# SimpleShield.net
KiCad netlist of a schematic drawn in EAGLE
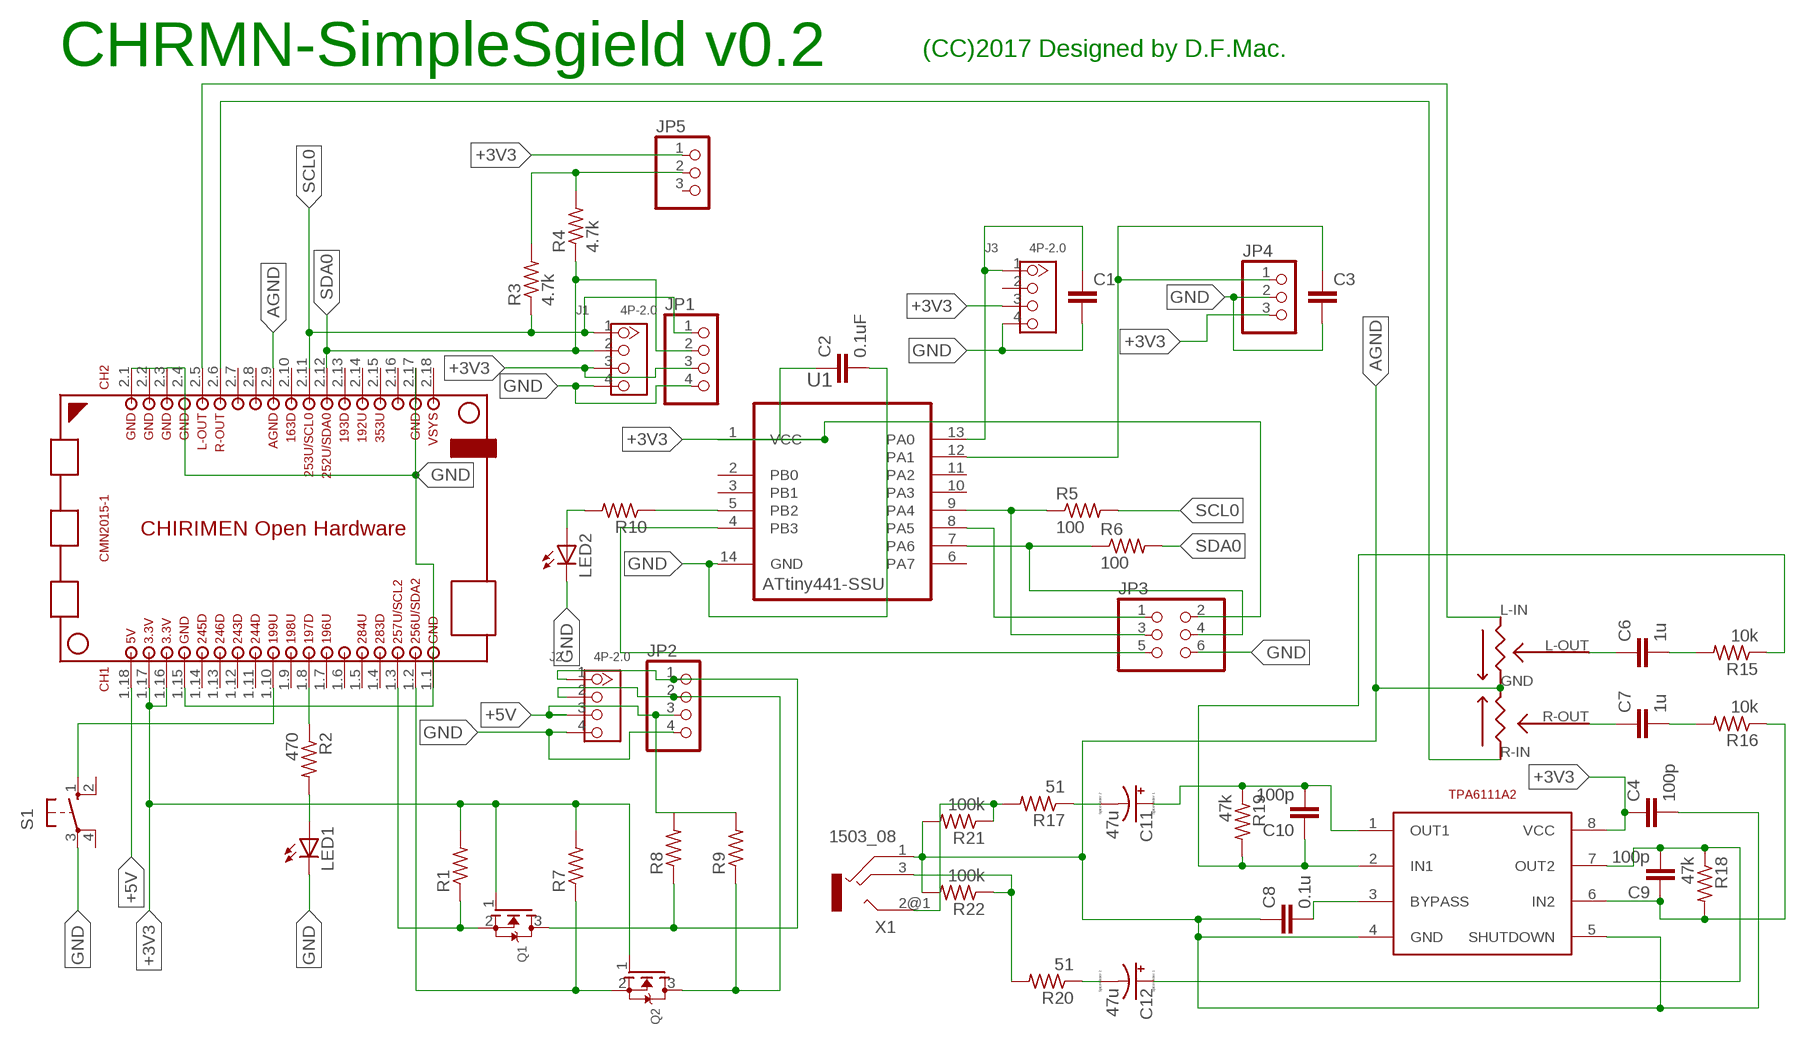
[diagram p0: schematic, sheet 1]

(export (version "E")
  (design (tool "Eeschema 10.0.6"))
  (components
    (comp (ref "C1")
      (value "C-EUC0805")
      (footprint "eagle-import:C0805")
      (libsource (lib "eagle-import") (part "C-EUC0805"))
    )
    (comp (ref "C2")
      (value "0.1uF")
      (footprint "eagle-import:C0805")
      (libsource (lib "eagle-import") (part "C-EUC0805"))
    )
    (comp (ref "C3")
      (value "C-EUC0805")
      (footprint "eagle-import:C0805")
      (libsource (lib "eagle-import") (part "C-EUC0805"))
    )
    (comp (ref "C4")
      (value "100p")
      (footprint "eagle-import:C0603K")
      (libsource (lib "eagle-import") (part "resistor_C-EUC0603K"))
    )
    (comp (ref "C6")
      (value "1u")
      (footprint "eagle-import:C0603K")
      (libsource (lib "eagle-import") (part "resistor_C-EUC0603K"))
    )
    (comp (ref "C7")
      (value "1u")
      (footprint "eagle-import:C0603K")
      (libsource (lib "eagle-import") (part "resistor_C-EUC0603K"))
    )
    (comp (ref "C8")
      (value "0.1u")
      (footprint "eagle-import:C0603K")
      (libsource (lib "eagle-import") (part "resistor_C-EUC0603K"))
    )
    (comp (ref "C9")
      (value "100p")
      (footprint "eagle-import:C0603K")
      (libsource (lib "eagle-import") (part "resistor_C-EUC0603K"))
    )
    (comp (ref "C10")
      (value "100p")
      (footprint "eagle-import:C0603K")
      (libsource (lib "eagle-import") (part "resistor_C-EUC0603K"))
    )
    (comp (ref "C11")
      (value "47u")
      (footprint "eagle-import:153CLV-0605")
      (libsource (lib "eagle-import") (part "CPOL-US153CLV-0605"))
    )
    (comp (ref "C12")
      (value "47u")
      (footprint "eagle-import:153CLV-0605")
      (libsource (lib "eagle-import") (part "CPOL-US153CLV-0605"))
    )
    (comp (ref "J1")
      (value "4P-2.0")
      (footprint "eagle-import:HW4-2.0")
      (libsource (lib "eagle-import") (part "GROVE-CONNECTOR-DIP(4P-2.0)"))
    )
    (comp (ref "J2")
      (value "4P-2.0")
      (footprint "eagle-import:HW4-2.0")
      (libsource (lib "eagle-import") (part "GROVE-CONNECTOR-DIP(4P-2.0)"))
    )
    (comp (ref "J3")
      (value "4P-2.0")
      (footprint "eagle-import:HW4-2.0")
      (libsource (lib "eagle-import") (part "GROVE-CONNECTOR-DIP(4P-2.0)"))
    )
    (comp (ref "JP1")
      (value "PINHD-1X4")
      (footprint "eagle-import:1X04")
      (libsource (lib "eagle-import") (part "PINHD-1X4"))
    )
    (comp (ref "JP2")
      (value "PINHD-1X4")
      (footprint "eagle-import:1X04")
      (libsource (lib "eagle-import") (part "PINHD-1X4"))
    )
    (comp (ref "JP3")
      (value "PINHD-2X3")
      (footprint "eagle-import:2X03")
      (libsource (lib "eagle-import") (part "PINHD-2X3"))
    )
    (comp (ref "JP4")
      (value "PINHD-1X3")
      (footprint "eagle-import:1X03")
      (libsource (lib "eagle-import") (part "PINHD-1X3"))
    )
    (comp (ref "JP5")
      (value "PINHD-1X3")
      (footprint "eagle-import:1X03")
      (libsource (lib "eagle-import") (part "PINHD-1X3"))
    )
    (comp (ref "LED1")
      (value "LED3MM")
      (footprint "eagle-import:LED3MM")
      (libsource (lib "eagle-import") (part "LED3MM"))
    )
    (comp (ref "LED2")
      (value "LED3MM")
      (footprint "eagle-import:LED3MM")
      (libsource (lib "eagle-import") (part "LED3MM"))
    )
    (comp (ref "Q1")
      (value "MOSFET-NREFLOW")
      (footprint "eagle-import:SOT23")
      (libsource (lib "eagle-import") (part "MOSFET-NREFLOW"))
    )
    (comp (ref "Q2")
      (value "MOSFET-NREFLOW")
      (footprint "eagle-import:SOT23")
      (libsource (lib "eagle-import") (part "MOSFET-NREFLOW"))
    )
    (comp (ref "R1")
      (value "R-US_R0603")
      (footprint "eagle-import:R0603")
      (libsource (lib "eagle-import") (part "R-US_R0603"))
    )
    (comp (ref "R2")
      (value "470")
      (footprint "eagle-import:R0603")
      (libsource (lib "eagle-import") (part "R-US_R0603"))
    )
    (comp (ref "R3")
      (value "4.7k")
      (footprint "eagle-import:R0603")
      (libsource (lib "eagle-import") (part "R-US_R0603"))
    )
    (comp (ref "R4")
      (value "4.7k")
      (footprint "eagle-import:R0603")
      (libsource (lib "eagle-import") (part "R-US_R0603"))
    )
    (comp (ref "R5")
      (value "100")
      (footprint "eagle-import:R0603")
      (libsource (lib "eagle-import") (part "R-US_R0603"))
    )
    (comp (ref "R6")
      (value "100")
      (footprint "eagle-import:R0603")
      (libsource (lib "eagle-import") (part "R-US_R0603"))
    )
    (comp (ref "R7")
      (value "R-US_R0603")
      (footprint "eagle-import:R0603")
      (libsource (lib "eagle-import") (part "R-US_R0603"))
    )
    (comp (ref "R8")
      (value "R-US_R0603")
      (footprint "eagle-import:R0603")
      (libsource (lib "eagle-import") (part "R-US_R0603"))
    )
    (comp (ref "R9")
      (value "R-US_R0603")
      (footprint "eagle-import:R0603")
      (libsource (lib "eagle-import") (part "R-US_R0603"))
    )
    (comp (ref "R10")
      (value "R-US_R0603")
      (footprint "eagle-import:R0603")
      (libsource (lib "eagle-import") (part "R-US_R0603"))
    )
    (comp (ref "R15")
      (value "10k")
      (footprint "eagle-import:R0603")
      (libsource (lib "eagle-import") (part "R-US_R0603"))
    )
    (comp (ref "R16")
      (value "10k")
      (footprint "eagle-import:R0603")
      (libsource (lib "eagle-import") (part "R-US_R0603"))
    )
    (comp (ref "R17")
      (value "51")
      (footprint "eagle-import:R0603")
      (libsource (lib "eagle-import") (part "R-US_R0603"))
    )
    (comp (ref "R18")
      (value "47k")
      (footprint "eagle-import:R0603")
      (libsource (lib "eagle-import") (part "R-US_R0603"))
    )
    (comp (ref "R19")
      (value "47k")
      (footprint "eagle-import:R0603")
      (libsource (lib "eagle-import") (part "R-US_R0603"))
    )
    (comp (ref "R20")
      (value "51")
      (footprint "eagle-import:R0603")
      (libsource (lib "eagle-import") (part "R-US_R0603"))
    )
    (comp (ref "R21")
      (value "100k")
      (footprint "eagle-import:R0603")
      (libsource (lib "eagle-import") (part "R-US_R0603"))
    )
    (comp (ref "R22")
      (value "100k")
      (footprint "eagle-import:R0603")
      (libsource (lib "eagle-import") (part "R-US_R0603"))
    )
    (comp (ref "S1")
      (value "10-XX")
      (footprint "eagle-import:B3F-10XX")
      (fields (field (name "MPN") "B3F-1000"))
      (libsource (lib "eagle-import") (part "10-XX"))
    )
    (comp (ref "U$1")
      (value "CMN2015-1SMALL")
      (footprint "eagle-import:CHMN2015-1-SMALL")
      (libsource (lib "eagle-import") (part "CMN2015-1SMALL"))
    )
    (comp (ref "U$4")
      (value "5PIN-RADIO-POT")
      (footprint "eagle-import:5PIN-RADIO-POT")
      (libsource (lib "eagle-import") (part "5PIN-RADIO-POT"))
    )
    (comp (ref "U$5")
      (value "TPA6111A2")
      (footprint "eagle-import:MSOP8")
      (libsource (lib "eagle-import") (part "TPA6111A2"))
    )
    (comp (ref "U1")
      (value "ATTINY44A-SSU")
      (footprint "eagle-import:SOIC127P600X175-14N")
      (libsource (lib "eagle-import") (part "ATTINY44A-SSU"))
    )
    (comp (ref "X1")
      (value "1503_08")
      (footprint "eagle-import:1503_08")
      (libsource (lib "eagle-import") (part "1503_?08"))
    )
  )
  (nets
    (net (code "1") (name "+3V3") (class "Default")
      (node (ref "C2") (pin "1") (pinfunction "1_1") (pintype "passive"))
      (node (ref "C4") (pin "1") (pinfunction "1_1") (pintype "passive"))
      (node (ref "J1") (pin "3") (pinfunction "3_3") (pintype "bidirectional"))
      (node (ref "J3") (pin "3") (pinfunction "3_3") (pintype "bidirectional"))
      (node (ref "JP1") (pin "3") (pinfunction "3_3") (pintype "passive"))
      (node (ref "JP3") (pin "2") (pinfunction "2_2") (pintype "passive"))
      (node (ref "JP4") (pin "3") (pinfunction "3_3") (pintype "passive"))
      (node (ref "JP5") (pin "1") (pinfunction "1_1") (pintype "passive"))
      (node (ref "Q1") (pin "1") (pinfunction "G_1") (pintype "bidirectional"))
      (node (ref "Q2") (pin "1") (pinfunction "G_1") (pintype "bidirectional"))
      (node (ref "R1") (pin "2") (pinfunction "2_2") (pintype "passive"))
      (node (ref "R7") (pin "2") (pinfunction "2_2") (pintype "passive"))
      (node (ref "U$1") (pin "1.16") (pinfunction "CH1-16_1.16") (pintype "bidirectional"))
      (node (ref "U$1") (pin "1.17") (pinfunction "CH1-17_1.17") (pintype "bidirectional"))
      (node (ref "U$5") (pin "8") (pinfunction "VCC_8") (pintype "bidirectional"))
      (node (ref "U1") (pin "1") (pinfunction "VCC_1") (pintype "power_in"))
    )
    (net (code "2") (name "+5V") (class "Default")
      (node (ref "J2") (pin "3") (pinfunction "3_3") (pintype "bidirectional"))
      (node (ref "JP2") (pin "3") (pinfunction "3_3") (pintype "passive"))
      (node (ref "R8") (pin "2") (pinfunction "2_2") (pintype "passive"))
      (node (ref "R9") (pin "2") (pinfunction "2_2") (pintype "passive"))
      (node (ref "U$1") (pin "1.18") (pinfunction "CH1-18_1.18") (pintype "bidirectional"))
    )
    (net (code "3") (name "AGND") (class "Default")
      (node (ref "C4") (pin "2") (pinfunction "2_2") (pintype "passive"))
      (node (ref "C8") (pin "1") (pinfunction "1_1") (pintype "passive"))
      (node (ref "R21") (pin "2") (pinfunction "2_2") (pintype "passive"))
      (node (ref "R22") (pin "2") (pinfunction "2_2") (pintype "passive"))
      (node (ref "U$1") (pin "2.9") (pinfunction "CH2-9_2.9") (pintype "bidirectional"))
      (node (ref "U$4") (pin "GND") (pinfunction "GND_GND") (pintype "bidirectional"))
      (node (ref "U$5") (pin "4") (pinfunction "GND_4") (pintype "bidirectional"))
      (node (ref "U$5") (pin "5") (pinfunction "SHUTDOWN_5") (pintype "bidirectional"))
      (node (ref "X1") (pin "1") (pinfunction "GND_1") (pintype "passive"))
    )
    (net (code "4") (name "GND") (class "Default")
      (node (ref "C1") (pin "2") (pinfunction "2_2") (pintype "passive"))
      (node (ref "C2") (pin "2") (pinfunction "2_2") (pintype "passive"))
      (node (ref "C3") (pin "2") (pinfunction "2_2") (pintype "passive"))
      (node (ref "J1") (pin "4") (pinfunction "4_4") (pintype "bidirectional"))
      (node (ref "J2") (pin "4") (pinfunction "4_4") (pintype "bidirectional"))
      (node (ref "J3") (pin "4") (pinfunction "4_4") (pintype "bidirectional"))
      (node (ref "JP1") (pin "4") (pinfunction "4_4") (pintype "passive"))
      (node (ref "JP2") (pin "4") (pinfunction "4_4") (pintype "passive"))
      (node (ref "JP3") (pin "6") (pinfunction "6_6") (pintype "passive"))
      (node (ref "JP4") (pin "2") (pinfunction "2_2") (pintype "passive"))
      (node (ref "LED1") (pin "K") (pinfunction "C_K") (pintype "passive"))
      (node (ref "LED2") (pin "K") (pinfunction "C_K") (pintype "passive"))
      (node (ref "S1") (pin "3") (pinfunction "P_3") (pintype "passive"))
      (node (ref "U$1") (pin "1.1") (pinfunction "CH1-1_1.1") (pintype "bidirectional"))
      (node (ref "U$1") (pin "1.15") (pinfunction "CH1-15_1.15") (pintype "bidirectional"))
      (node (ref "U$1") (pin "2.1") (pinfunction "CH2-1_2.1") (pintype "bidirectional"))
      (node (ref "U$1") (pin "2.17") (pinfunction "CH2-17_2.17") (pintype "bidirectional"))
      (node (ref "U$1") (pin "2.2") (pinfunction "CH2-2_2.2") (pintype "bidirectional"))
      (node (ref "U$1") (pin "2.3") (pinfunction "CH2-3_2.3") (pintype "bidirectional"))
      (node (ref "U$1") (pin "2.4") (pinfunction "CH2-4_2.4") (pintype "bidirectional"))
      (node (ref "U1") (pin "14") (pinfunction "GND_14") (pintype "power_in"))
    )
    (net (code "5") (name "Net-(C6-Pad2)") (class "Default")
      (node (ref "C6") (pin "2") (pinfunction "2_2") (pintype "passive"))
      (node (ref "R15") (pin "2") (pinfunction "2_2") (pintype "passive"))
    )
    (net (code "6") (name "Net-(C7-Pad2)") (class "Default")
      (node (ref "C7") (pin "2") (pinfunction "2_2") (pintype "passive"))
      (node (ref "R16") (pin "2") (pinfunction "2_2") (pintype "passive"))
    )
    (net (code "7") (name "Net-(C11-Pad-)") (class "Default")
      (node (ref "C11") (pin "-") (pinfunction "-_-") (pintype "passive"))
      (node (ref "R17") (pin "1") (pinfunction "1_1") (pintype "passive"))
    )
    (net (code "8") (name "Net-(C12-Pad-)") (class "Default")
      (node (ref "C12") (pin "-") (pinfunction "-_-") (pintype "passive"))
      (node (ref "R20") (pin "1") (pinfunction "1_1") (pintype "passive"))
    )
    (net (code "9") (name "Net-(JP5-Pad2)") (class "Default")
      (node (ref "JP5") (pin "2") (pinfunction "2_2") (pintype "passive"))
      (node (ref "R3") (pin "2") (pinfunction "2_2") (pintype "passive"))
      (node (ref "R4") (pin "2") (pinfunction "2_2") (pintype "passive"))
    )
    (net (code "10") (name "Net-(LED1-PadA)") (class "Default")
      (node (ref "LED1") (pin "A") (pinfunction "A_A") (pintype "passive"))
      (node (ref "R2") (pin "2") (pinfunction "2_2") (pintype "passive"))
    )
    (net (code "11") (name "Net-(LED2-PadA)") (class "Default")
      (node (ref "LED2") (pin "A") (pinfunction "A_A") (pintype "passive"))
      (node (ref "R10") (pin "2") (pinfunction "2_2") (pintype "passive"))
    )
    (net (code "12") (name "Net-(Q1-D)") (class "Default")
      (node (ref "J2") (pin "1") (pinfunction "1_1") (pintype "bidirectional"))
      (node (ref "JP2") (pin "1") (pinfunction "1_1") (pintype "passive"))
      (node (ref "Q1") (pin "3") (pinfunction "D_3") (pintype "bidirectional"))
      (node (ref "R8") (pin "1") (pinfunction "1_1") (pintype "passive"))
    )
    (net (code "13") (name "Net-(Q1-S)") (class "Default")
      (node (ref "Q1") (pin "2") (pinfunction "S_2") (pintype "bidirectional"))
      (node (ref "R1") (pin "1") (pinfunction "1_1") (pintype "passive"))
      (node (ref "U$1") (pin "1.3") (pinfunction "CH1-3_1.3") (pintype "bidirectional"))
    )
    (net (code "14") (name "Net-(Q2-D)") (class "Default")
      (node (ref "J2") (pin "2") (pinfunction "2_2") (pintype "bidirectional"))
      (node (ref "JP2") (pin "2") (pinfunction "2_2") (pintype "passive"))
      (node (ref "Q2") (pin "3") (pinfunction "D_3") (pintype "bidirectional"))
      (node (ref "R9") (pin "1") (pinfunction "1_1") (pintype "passive"))
    )
    (net (code "15") (name "Net-(Q2-S)") (class "Default")
      (node (ref "Q2") (pin "2") (pinfunction "S_2") (pintype "bidirectional"))
      (node (ref "R7") (pin "1") (pinfunction "1_1") (pintype "passive"))
      (node (ref "U$1") (pin "1.2") (pinfunction "CH1-2_1.2") (pintype "bidirectional"))
    )
    (net (code "16") (name "Net-(S1-S)") (class "Default")
      (node (ref "S1") (pin "1") (pinfunction "S_1") (pintype "passive"))
      (node (ref "U$1") (pin "1.10") (pinfunction "CH1-10_1.10") (pintype "bidirectional"))
    )
    (net (code "17") (name "Net-(U$1-CH1-8)") (class "Default")
      (node (ref "R2") (pin "1") (pinfunction "1_1") (pintype "passive"))
      (node (ref "U$1") (pin "1.8") (pinfunction "CH1-8_1.8") (pintype "bidirectional"))
    )
    (net (code "18") (name "Net-(U$1-CH2-5)") (class "Default")
      (node (ref "U$1") (pin "2.5") (pinfunction "CH2-5_2.5") (pintype "bidirectional"))
      (node (ref "U$4") (pin "L-IN") (pinfunction "IN-L_L-IN") (pintype "bidirectional"))
    )
    (net (code "19") (name "Net-(U$1-CH2-6)") (class "Default")
      (node (ref "U$1") (pin "2.6") (pinfunction "CH2-6_2.6") (pintype "bidirectional"))
      (node (ref "U$4") (pin "R-IN") (pinfunction "IN-R_R-IN") (pintype "bidirectional"))
    )
    (net (code "20") (name "Net-(U$4-OUT-L)") (class "Default")
      (node (ref "C6") (pin "1") (pinfunction "1_1") (pintype "passive"))
      (node (ref "U$4") (pin "L-OUT") (pinfunction "OUT-L_L-OUT") (pintype "bidirectional"))
    )
    (net (code "21") (name "Net-(U$4-OUT-R)") (class "Default")
      (node (ref "C7") (pin "1") (pinfunction "1_1") (pintype "passive"))
      (node (ref "U$4") (pin "R-OUT") (pinfunction "OUT-R_R-OUT") (pintype "bidirectional"))
    )
    (net (code "22") (name "Net-(U$5-BYPASS)") (class "Default")
      (node (ref "C8") (pin "2") (pinfunction "2_2") (pintype "passive"))
      (node (ref "U$5") (pin "3") (pinfunction "BYPASS_3") (pintype "bidirectional"))
    )
    (net (code "23") (name "Net-(U$5-IN1)") (class "Default")
      (node (ref "C10") (pin "1") (pinfunction "1_1") (pintype "passive"))
      (node (ref "R15") (pin "1") (pinfunction "1_1") (pintype "passive"))
      (node (ref "R19") (pin "2") (pinfunction "2_2") (pintype "passive"))
      (node (ref "U$5") (pin "2") (pinfunction "IN1_2") (pintype "bidirectional"))
    )
    (net (code "24") (name "Net-(U$5-IN2)") (class "Default")
      (node (ref "C9") (pin "1") (pinfunction "1_1") (pintype "passive"))
      (node (ref "R16") (pin "1") (pinfunction "1_1") (pintype "passive"))
      (node (ref "R18") (pin "2") (pinfunction "2_2") (pintype "passive"))
      (node (ref "U$5") (pin "6") (pinfunction "IN2_6") (pintype "bidirectional"))
    )
    (net (code "25") (name "Net-(U$5-OUT1)") (class "Default")
      (node (ref "C10") (pin "2") (pinfunction "2_2") (pintype "passive"))
      (node (ref "C11") (pin "+") (pinfunction "+_+") (pintype "passive"))
      (node (ref "R19") (pin "1") (pinfunction "1_1") (pintype "passive"))
      (node (ref "U$5") (pin "1") (pinfunction "OUT1_1") (pintype "bidirectional"))
    )
    (net (code "26") (name "Net-(U$5-OUT2)") (class "Default")
      (node (ref "C12") (pin "+") (pinfunction "+_+") (pintype "passive"))
      (node (ref "C9") (pin "2") (pinfunction "2_2") (pintype "passive"))
      (node (ref "R18") (pin "1") (pinfunction "1_1") (pintype "passive"))
      (node (ref "U$5") (pin "7") (pinfunction "OUT2_7") (pintype "bidirectional"))
    )
    (net (code "27") (name "Net-(U1-PA0)") (class "Default")
      (node (ref "C1") (pin "1") (pinfunction "1_1") (pintype "passive"))
      (node (ref "J3") (pin "1") (pinfunction "1_1") (pintype "bidirectional"))
      (node (ref "U1") (pin "13") (pinfunction "PA0_13") (pintype "bidirectional"))
    )
    (net (code "28") (name "Net-(U1-PA1)") (class "Default")
      (node (ref "C3") (pin "1") (pinfunction "1_1") (pintype "passive"))
      (node (ref "JP4") (pin "1") (pinfunction "1_1") (pintype "passive"))
      (node (ref "U1") (pin "12") (pinfunction "PA1_12") (pintype "bidirectional"))
    )
    (net (code "29") (name "Net-(U1-PA4)") (class "Default")
      (node (ref "JP3") (pin "3") (pinfunction "3_3") (pintype "passive"))
      (node (ref "R5") (pin "1") (pinfunction "1_1") (pintype "passive"))
      (node (ref "U1") (pin "9") (pinfunction "PA4_9") (pintype "bidirectional"))
    )
    (net (code "30") (name "Net-(U1-PA5)") (class "Default")
      (node (ref "JP3") (pin "1") (pinfunction "1_1") (pintype "passive"))
      (node (ref "U1") (pin "8") (pinfunction "PA5_8") (pintype "bidirectional"))
    )
    (net (code "31") (name "Net-(U1-PA6)") (class "Default")
      (node (ref "JP3") (pin "4") (pinfunction "4_4") (pintype "passive"))
      (node (ref "R6") (pin "1") (pinfunction "1_1") (pintype "passive"))
      (node (ref "U1") (pin "7") (pinfunction "PA6_7") (pintype "bidirectional"))
    )
    (net (code "32") (name "Net-(U1-PB2)") (class "Default")
      (node (ref "R10") (pin "1") (pinfunction "1_1") (pintype "passive"))
      (node (ref "U1") (pin "5") (pinfunction "PB2_5") (pintype "bidirectional"))
    )
    (net (code "33") (name "Net-(U1-PB3)") (class "Default")
      (node (ref "JP3") (pin "5") (pinfunction "5_5") (pintype "passive"))
      (node (ref "U1") (pin "4") (pinfunction "PB3_4") (pintype "bidirectional"))
    )
    (net (code "34") (name "Net-(X1-L)") (class "Default")
      (node (ref "R17") (pin "2") (pinfunction "2_2") (pintype "passive"))
      (node (ref "R21") (pin "1") (pinfunction "1_1") (pintype "passive"))
      (node (ref "X1") (pin "2@1") (pinfunction "L_2@1") (pintype "passive"))
    )
    (net (code "35") (name "Net-(X1-R)") (class "Default")
      (node (ref "R20") (pin "2") (pinfunction "2_2") (pintype "passive"))
      (node (ref "R22") (pin "1") (pinfunction "1_1") (pintype "passive"))
      (node (ref "X1") (pin "3") (pinfunction "R_3") (pintype "passive"))
    )
    (net (code "36") (name "SCL0") (class "Default")
      (node (ref "J1") (pin "1") (pinfunction "1_1") (pintype "bidirectional"))
      (node (ref "JP1") (pin "1") (pinfunction "1_1") (pintype "passive"))
      (node (ref "R3") (pin "1") (pinfunction "1_1") (pintype "passive"))
      (node (ref "R5") (pin "2") (pinfunction "2_2") (pintype "passive"))
      (node (ref "U$1") (pin "2.11") (pinfunction "CH2-11_2.11") (pintype "bidirectional"))
    )
    (net (code "37") (name "SDA0") (class "Default")
      (node (ref "J1") (pin "2") (pinfunction "2_2") (pintype "bidirectional"))
      (node (ref "JP1") (pin "2") (pinfunction "2_2") (pintype "passive"))
      (node (ref "R4") (pin "1") (pinfunction "1_1") (pintype "passive"))
      (node (ref "R6") (pin "2") (pinfunction "2_2") (pintype "passive"))
      (node (ref "U$1") (pin "2.12") (pinfunction "CH2-12_2.12") (pintype "bidirectional"))
    )
    (net (code "38") (name "unconnected-(J3-Pad2)") (class "Default")
      (node (ref "J3") (pin "2") (pinfunction "2_2") (pintype "bidirectional"))
    )
    (net (code "39") (name "unconnected-(JP5-Pad3)") (class "Default")
      (node (ref "JP5") (pin "3") (pinfunction "3_3") (pintype "passive"))
    )
    (net (code "40") (name "unconnected-(S1-P1-Pad4)") (class "Default")
      (node (ref "S1") (pin "4") (pinfunction "P1_4") (pintype "passive"))
    )
    (net (code "41") (name "unconnected-(S1-S1-Pad2)") (class "Default")
      (node (ref "S1") (pin "2") (pinfunction "S1_2") (pintype "passive"))
    )
    (net (code "42") (name "unconnected-(U$1-CH1-4-Pad1.4)") (class "Default")
      (node (ref "U$1") (pin "1.4") (pinfunction "CH1-4_1.4") (pintype "bidirectional"))
    )
    (net (code "43") (name "unconnected-(U$1-CH1-5-Pad1.5)") (class "Default")
      (node (ref "U$1") (pin "1.5") (pinfunction "CH1-5_1.5") (pintype "bidirectional"))
    )
    (net (code "44") (name "unconnected-(U$1-CH1-6-Pad1.6)") (class "Default")
      (node (ref "U$1") (pin "1.6") (pinfunction "CH1-6_1.6") (pintype "bidirectional"))
    )
    (net (code "45") (name "unconnected-(U$1-CH1-7-Pad1.7)") (class "Default")
      (node (ref "U$1") (pin "1.7") (pinfunction "CH1-7_1.7") (pintype "bidirectional"))
    )
    (net (code "46") (name "unconnected-(U$1-CH1-9-Pad1.9)") (class "Default")
      (node (ref "U$1") (pin "1.9") (pinfunction "CH1-9_1.9") (pintype "bidirectional"))
    )
    (net (code "47") (name "unconnected-(U$1-CH1-11-Pad1.11)") (class "Default")
      (node (ref "U$1") (pin "1.11") (pinfunction "CH1-11_1.11") (pintype "bidirectional"))
    )
    (net (code "48") (name "unconnected-(U$1-CH1-12-Pad1.12)") (class "Default")
      (node (ref "U$1") (pin "1.12") (pinfunction "CH1-12_1.12") (pintype "bidirectional"))
    )
    (net (code "49") (name "unconnected-(U$1-CH1-13-Pad1.13)") (class "Default")
      (node (ref "U$1") (pin "1.13") (pinfunction "CH1-13_1.13") (pintype "bidirectional"))
    )
    (net (code "50") (name "unconnected-(U$1-CH1-14-Pad1.14)") (class "Default")
      (node (ref "U$1") (pin "1.14") (pinfunction "CH1-14_1.14") (pintype "bidirectional"))
    )
    (net (code "51") (name "unconnected-(U$1-CH2-7-Pad2.7)") (class "Default")
      (node (ref "U$1") (pin "2.7") (pinfunction "CH2-7_2.7") (pintype "bidirectional"))
    )
    (net (code "52") (name "unconnected-(U$1-CH2-8-Pad2.8)") (class "Default")
      (node (ref "U$1") (pin "2.8") (pinfunction "CH2-8_2.8") (pintype "bidirectional"))
    )
    (net (code "53") (name "unconnected-(U$1-CH2-10-Pad2.10)") (class "Default")
      (node (ref "U$1") (pin "2.10") (pinfunction "CH2-10_2.10") (pintype "bidirectional"))
    )
    (net (code "54") (name "unconnected-(U$1-CH2-13-Pad2.13)") (class "Default")
      (node (ref "U$1") (pin "2.13") (pinfunction "CH2-13_2.13") (pintype "bidirectional"))
    )
    (net (code "55") (name "unconnected-(U$1-CH2-14-Pad2.14)") (class "Default")
      (node (ref "U$1") (pin "2.14") (pinfunction "CH2-14_2.14") (pintype "bidirectional"))
    )
    (net (code "56") (name "unconnected-(U$1-CH2-15-Pad2.15)") (class "Default")
      (node (ref "U$1") (pin "2.15") (pinfunction "CH2-15_2.15") (pintype "bidirectional"))
    )
    (net (code "57") (name "unconnected-(U$1-CH2-16-Pad2.16)") (class "Default")
      (node (ref "U$1") (pin "2.16") (pinfunction "CH2-16_2.16") (pintype "bidirectional"))
    )
    (net (code "58") (name "unconnected-(U$1-CH2-18-Pad2.18)") (class "Default")
      (node (ref "U$1") (pin "2.18") (pinfunction "CH2-18_2.18") (pintype "bidirectional"))
    )
    (net (code "59") (name "unconnected-(U$1-HOLE1-PadO1)") (class "Default")
      (node (ref "U$1") (pin "O1") (pinfunction "HOLE1_O1") (pintype "bidirectional"))
    )
    (net (code "60") (name "unconnected-(U$1-HOLE2-PadO2)") (class "Default")
      (node (ref "U$1") (pin "O2") (pinfunction "HOLE2_O2") (pintype "bidirectional"))
    )
    (net (code "61") (name "unconnected-(U1-PA2-Pad11)") (class "Default")
      (node (ref "U1") (pin "11") (pinfunction "PA2_11") (pintype "bidirectional"))
    )
    (net (code "62") (name "unconnected-(U1-PA3-Pad10)") (class "Default")
      (node (ref "U1") (pin "10") (pinfunction "PA3_10") (pintype "bidirectional"))
    )
    (net (code "63") (name "unconnected-(U1-PA7-Pad6)") (class "Default")
      (node (ref "U1") (pin "6") (pinfunction "PA7_6") (pintype "bidirectional"))
    )
    (net (code "64") (name "unconnected-(U1-PB0-Pad2)") (class "Default")
      (node (ref "U1") (pin "2") (pinfunction "PB0_2") (pintype "bidirectional"))
    )
    (net (code "65") (name "unconnected-(U1-PB1-Pad3)") (class "Default")
      (node (ref "U1") (pin "3") (pinfunction "PB1_3") (pintype "bidirectional"))
    )
    (net (code "66") (name "unconnected-(X1-2-Pad2@2)") (class "Default")
      (node (ref "X1") (pin "2@2") (pinfunction "2_2@2") (pintype "passive"))
    )
  )
)
